# pierce-test-board3.net
KiCad netlist of a schematic drawn in EAGLE
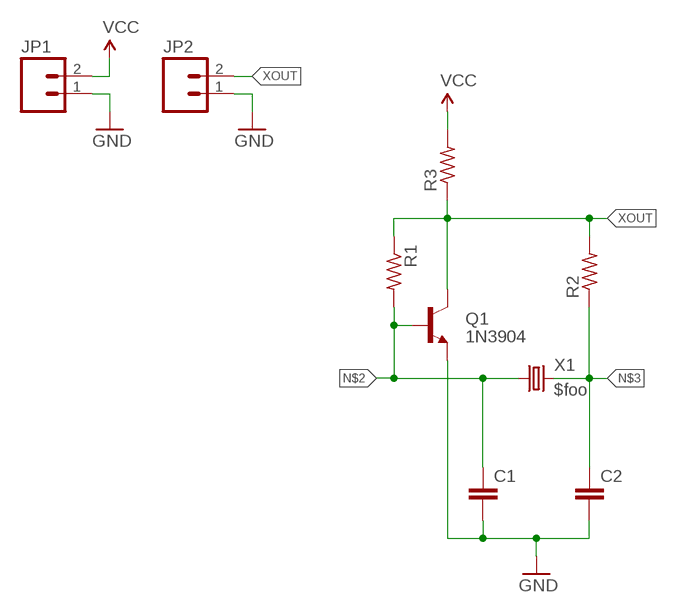
[diagram p0: schematic, sheet 1]

(export (version "E")
  (design (tool "Eeschema 10.0.6"))
  (components
    (comp (ref "C1")
      (value "CAPACITOR-CERAMIC025-024X044")
      (footprint "eagle-import:C025-024X044")
      (libsource (lib "eagle-import") (part "CAPACITOR-CERAMIC025-024X044"))
    )
    (comp (ref "C2")
      (value "CAPACITOR-CERAMIC025-024X044")
      (footprint "eagle-import:C025-024X044")
      (libsource (lib "eagle-import") (part "CAPACITOR-CERAMIC025-024X044"))
    )
    (comp (ref "JP1")
      (value "M02PTH")
      (footprint "eagle-import:1X02")
      (libsource (lib "eagle-import") (part "M02PTH"))
    )
    (comp (ref "JP2")
      (value "M02PTH")
      (footprint "eagle-import:1X02")
      (libsource (lib "eagle-import") (part "M02PTH"))
    )
    (comp (ref "Q1")
      (value "1N3904")
      (footprint "eagle-import:TO-92-AMMO")
      (libsource (lib "eagle-import") (part "TRANSISTOR_NPNTO-92-AMMO-EBC"))
    )
    (comp (ref "R1")
      (value "RESISTORPTH-AXIAL-5.08MM")
      (footprint "eagle-import:RESISTOR-AXIAL-PTH-5.08MM")
      (libsource (lib "eagle-import") (part "RESISTORPTH-AXIAL-5.08MM"))
    )
    (comp (ref "R2")
      (value "RESISTORPTH-AXIAL-5.08MM")
      (footprint "eagle-import:RESISTOR-AXIAL-PTH-5.08MM")
      (libsource (lib "eagle-import") (part "RESISTORPTH-AXIAL-5.08MM"))
    )
    (comp (ref "R3")
      (value "RESISTORPTH-AXIAL-5.08MM")
      (footprint "eagle-import:RESISTOR-AXIAL-PTH-5.08MM")
      (libsource (lib "eagle-import") (part "RESISTORPTH-AXIAL-5.08MM"))
    )
    (comp (ref "X1")
      (value "$foo")
      (footprint "eagle-import:HC49U-V")
      (libsource (lib "eagle-import") (part "CRYSTALHC49UV"))
    )
  )
  (nets
    (net (code "1") (name "GND") (class "Default")
      (node (ref "C1") (pin "2") (pinfunction "2_2") (pintype "passive"))
      (node (ref "C2") (pin "2") (pinfunction "2_2") (pintype "passive"))
      (node (ref "JP1") (pin "1") (pinfunction "1_1") (pintype "passive"))
      (node (ref "JP2") (pin "1") (pinfunction "1_1") (pintype "passive"))
      (node (ref "Q1") (pin "1") (pinfunction "E_1") (pintype "passive"))
    )
    (net (code "2") (name "N$2") (class "Default")
      (node (ref "C1") (pin "1") (pinfunction "1_1") (pintype "passive"))
      (node (ref "Q1") (pin "2") (pinfunction "B_2") (pintype "passive"))
      (node (ref "R1") (pin "P$2") (pinfunction "2_P$2") (pintype "passive"))
      (node (ref "X1") (pin "1") (pinfunction "1_1") (pintype "passive"))
    )
    (net (code "3") (name "N$3") (class "Default")
      (node (ref "C2") (pin "1") (pinfunction "1_1") (pintype "passive"))
      (node (ref "R2") (pin "P$1") (pinfunction "1_P$1") (pintype "passive"))
      (node (ref "X1") (pin "2") (pinfunction "2_2") (pintype "passive"))
    )
    (net (code "4") (name "VCC") (class "Default")
      (node (ref "JP1") (pin "2") (pinfunction "2_2") (pintype "passive"))
      (node (ref "R3") (pin "P$2") (pinfunction "2_P$2") (pintype "passive"))
    )
    (net (code "5") (name "XOUT") (class "Default")
      (node (ref "JP2") (pin "2") (pinfunction "2_2") (pintype "passive"))
      (node (ref "Q1") (pin "3") (pinfunction "C_3") (pintype "passive"))
      (node (ref "R1") (pin "P$1") (pinfunction "1_P$1") (pintype "passive"))
      (node (ref "R2") (pin "P$2") (pinfunction "2_P$2") (pintype "passive"))
      (node (ref "R3") (pin "P$1") (pinfunction "1_P$1") (pintype "passive"))
    )
  )
)
